# Flowmeter.net
KiCad netlist of a schematic drawn in Altium Designer
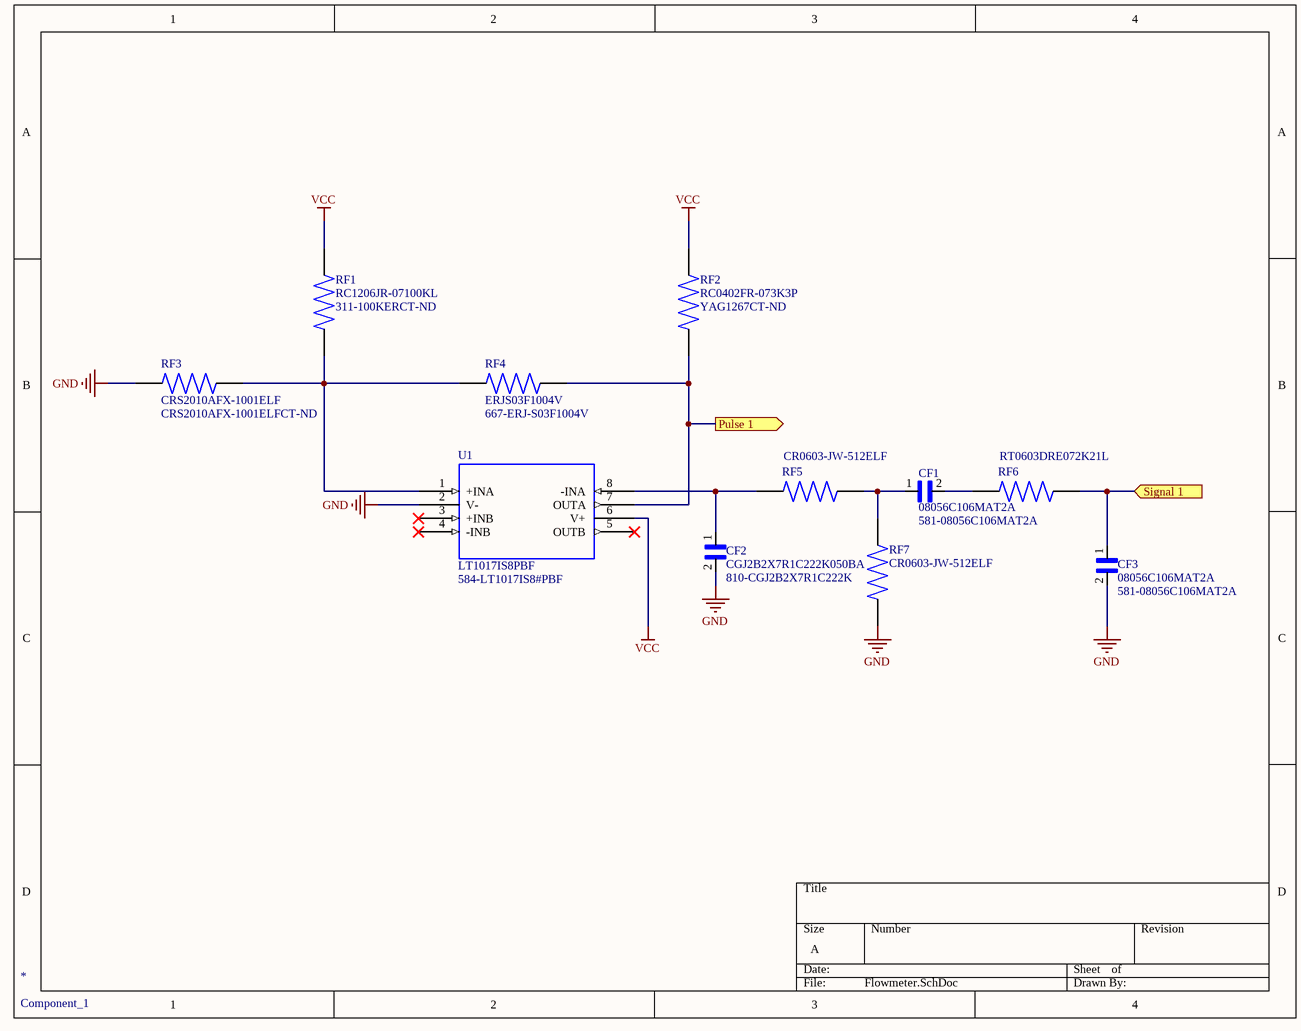
[diagram p0: Flowmeter.SchDoc]

(export (version "E")
  (design (tool "Eeschema 10.0.6"))
  (components
    (comp (ref "*") (value "Component_1") (libsource (lib "Schlib1") (part "Component_1")))
    (comp (ref "CF1")
      (value "08056C106MAT2A")
      (footprint "CAPC2012X152N")
      (description "0805 10 uF 6.3 V Â±20 % Tolerance X7R SMT Multilayer Ceramic Capacitor")
      (fields (field (name "SUPPLIER PART NUMBER 1") "581-08056C106MAT2A"))
      (libsource (lib "") (part "08056C106MAT2A_1"))
    )
    (comp (ref "CF2")
      (value "CGJ2B2X7R1C222K050BA")
      (footprint "CAPC1005X55N")
      (description "High Reliability - Autograde Plus+, Reel Size: 7\" (180mm)")
      (fields (field (name "SUPPLIER PART NUMBER 1") "810-CGJ2B2X7R1C222K"))
      (libsource (lib "2200pF_Cap_CGJ2B2X7R1C222K050BA") (part "CGJ2B2X7R1C222K050BA"))
    )
    (comp (ref "CF3")
      (value "08056C106MAT2A")
      (footprint "CAPC2012X152N")
      (description "0805 10 uF 6.3 V Â±20 % Tolerance X7R SMT Multilayer Ceramic Capacitor")
      (fields (field (name "SUPPLIER PART NUMBER 1") "581-08056C106MAT2A"))
      (libsource (lib "10uF_Cap_08056C106MAT2A") (part "08056C106MAT2A"))
    )
    (comp (ref "RF1")
      (value "RC1206JR-07100KL")
      (footprint "RESC3116X65N")
      (description "Carbon film resistor 100 kâ„¦ SMD 1206 0.25 W 5 % 200 ppm Yageo RC1206JR-07100KL 1 pc(s)")
      (fields (field (name "SUPPLIER PART NUMBER 1") "311-100KERCT-ND"))
      (libsource (lib "100K_Res_RC1206JR-07100KL") (part "RC1206JR-07100KL"))
    )
    (comp (ref "RF2")
      (value "RC0402FR-073K3P")
      (footprint "RESC1005X40N")
      (description "Chip Resistor Surface Mount")
      (fields (field (name "SUPPLIER PART NUMBER 1") "YAG1267CT-ND"))
      (libsource (lib "3.3K_Res_RC0402FR-073K3P") (part "RC0402FR-073K3P"))
    )
    (comp (ref "RF3")
      (value "CRS2010AFX-1001ELF")
      (footprint "RESC5025X70N")
      (fields (field (name "SUPPLIER PART NUMBER 1") "CRS2010AFX-1001ELFCT-ND"))
      (libsource (lib "1K_Res_CRS2010AFX-1001ELF") (part "CRS2010AFX-1001ELF"))
    )
    (comp (ref "RF4")
      (value "ERJS03F1004V")
      (footprint "RES_ERJS03F1004V")
      (description "Res Thick Film 0603 1M Ohm 1% 0.1W(1/10W) Â±100ppm/Â°C Sulfur Resistant Pad SMD Automotive T/R")
      (fields
        (field (name "MP") "ERJ-S03F1004V")
        (field (name "MF") "Panasonic")
        (field (name "SUPPLIER PART NUMBER 1") "667-ERJ-S03F1004V")
      )
      (libsource (lib "1M_Res_ERJS03F1004V") (part "ERJS03F1004V"))
    )
    (comp (ref "RF5")
      (value "CR0603-JW-512ELF")
      (footprint "RESC1608X55N")
      (description "Resistor Thick Film 0603 5.1k Ohm 5% 1/10 Watt Â±200ppm Â°C Surface Mount Paper Tape On Plastic Reel")
      (libsource (lib "5.1K_Res_CR0603-JW-512ELF") (part "CR0603-JW-512ELF"))
    )
    (comp (ref "RF6")
      (value "RT0603DRE072K21L")
      (footprint "RESC1608X55N")
      (description "RES SMD 2.21KOHM 0.5% 1/10W 0603")
      (libsource (lib "2.21K_Res_RT0603DRE072K21L") (part "RT0603DRE072K21L"))
    )
    (comp (ref "RF7")
      (value "CR0603-JW-512ELF")
      (footprint "RESC1608X55N")
      (description "Resistor Thick Film 0603 5.1k Ohm 5% 1/10 Watt Â±200ppm Â°C Surface Mount Paper Tape On Plastic Reel")
      (libsource (lib "5.1K_Res_CR0603-JW-512ELF") (part "CR0603-JW-512ELF"))
    )
    (comp (ref "U1")
      (value "LT1017IS8PBF")
      (footprint "SO-8_S")
      (description "Comparator General Purpose Pull Up 8-SOIC")
      (fields
        (field (name "MF") "Analog Devices")
        (field (name "MP") "LT1017IS8#PBF")
        (field (name "SUPPLIER PART NUMBER 1") "584-LT1017IS8#PBF")
      )
      (libsource (lib "Comparator_LT1017IS8PBF") (part "LT1017IS8PBF"))
    )
  )
  (nets
    (net (code "1") (name "/Pulse 1") (class "Default")
      (node (ref "RF2") (pin "2") (pinfunction "2_2") (pintype "passive"))
      (node (ref "RF4") (pin "2") (pinfunction "2_2") (pintype "passive"))
      (node (ref "U1") (pin "7") (pinfunction "OUTA_7") (pintype "output"))
    )
    (net (code "2") (name "/Signal 1") (class "Default")
      (node (ref "CF3") (pin "1") (pinfunction "1_1") (pintype "passive"))
      (node (ref "RF6") (pin "2") (pinfunction "2_2") (pintype "passive"))
    )
    (net (code "3") (name "GND") (class "Default")
      (node (ref "CF2") (pin "2") (pinfunction "2_2") (pintype "passive"))
      (node (ref "CF3") (pin "2") (pinfunction "2_2") (pintype "passive"))
      (node (ref "RF3") (pin "1") (pinfunction "1_1") (pintype "passive"))
      (node (ref "RF7") (pin "2") (pinfunction "2_2") (pintype "passive"))
      (node (ref "U1") (pin "2") (pinfunction "V-_2") (pintype "power_in"))
    )
    (net (code "4") (name "Net-(CF1-Pad1)") (class "Default")
      (node (ref "CF1") (pin "1") (pinfunction "1_1") (pintype "passive"))
      (node (ref "RF5") (pin "2") (pinfunction "2_2") (pintype "passive"))
      (node (ref "RF7") (pin "1") (pinfunction "1_1") (pintype "passive"))
    )
    (net (code "5") (name "Net-(CF1-Pad2)") (class "Default")
      (node (ref "CF1") (pin "2") (pinfunction "2_2") (pintype "passive"))
      (node (ref "RF6") (pin "1") (pinfunction "1_1") (pintype "passive"))
    )
    (net (code "6") (name "Net-(U1-+INA)") (class "Default")
      (node (ref "RF1") (pin "2") (pinfunction "2_2") (pintype "passive"))
      (node (ref "RF3") (pin "2") (pinfunction "2_2") (pintype "passive"))
      (node (ref "RF4") (pin "1") (pinfunction "1_1") (pintype "passive"))
      (node (ref "U1") (pin "1") (pinfunction "+INA_1") (pintype "input"))
    )
    (net (code "7") (name "Net-(U1--INA)") (class "Default")
      (node (ref "CF2") (pin "1") (pinfunction "1_1") (pintype "passive"))
      (node (ref "RF5") (pin "1") (pinfunction "1_1") (pintype "passive"))
      (node (ref "U1") (pin "8") (pinfunction "-INA_8") (pintype "input"))
    )
    (net (code "8") (name "VCC") (class "Default")
      (node (ref "RF1") (pin "1") (pinfunction "1_1") (pintype "passive"))
      (node (ref "RF2") (pin "1") (pinfunction "1_1") (pintype "passive"))
      (node (ref "U1") (pin "6") (pinfunction "V+_6") (pintype "power_in"))
    )
    (net (code "9") (name "unconnected-(U1-+INB-Pad3)") (class "Default")
      (node (ref "U1") (pin "3") (pinfunction "+INB_3") (pintype "input+no_connect"))
    )
    (net (code "10") (name "unconnected-(U1--INB-Pad4)") (class "Default")
      (node (ref "U1") (pin "4") (pinfunction "-INB_4") (pintype "input+no_connect"))
    )
    (net (code "11") (name "unconnected-(U1-OUTB-Pad5)") (class "Default")
      (node (ref "U1") (pin "5") (pinfunction "OUTB_5") (pintype "output+no_connect"))
    )
  )
)
